# CS301_14.net
KiCad netlist of a schematic drawn in Altium Designer
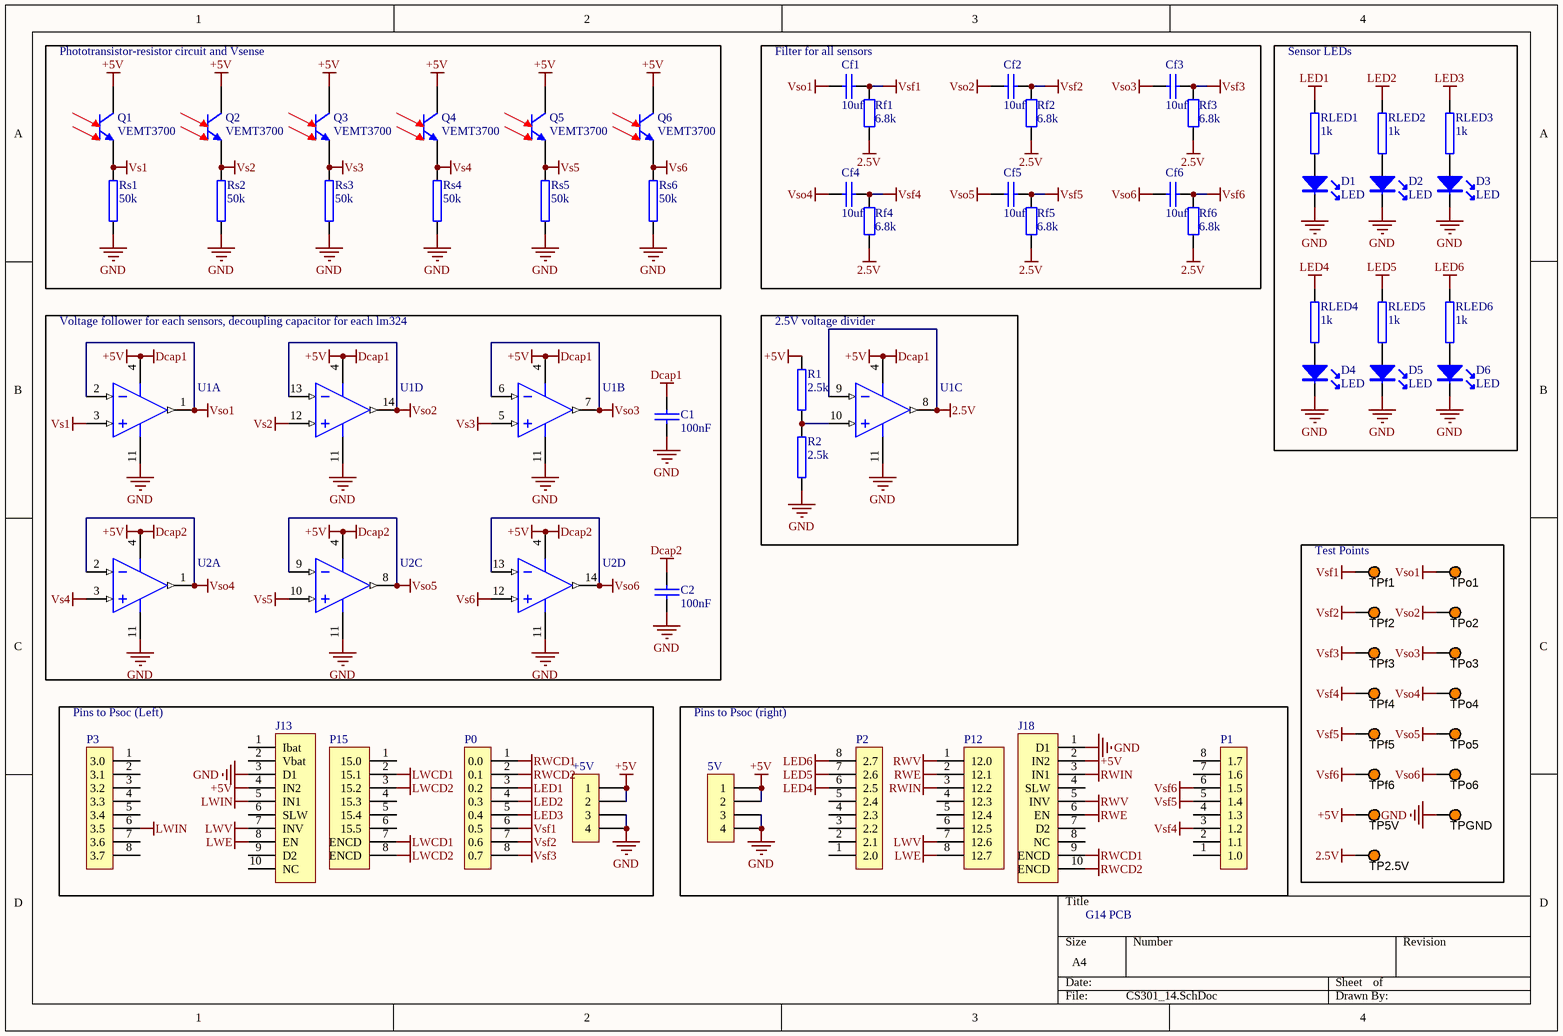
[diagram p0: CS301_14.SchDoc]

(export (version "E")
  (design (tool "Eeschema 10.0.6"))
  (components
    (comp (ref "+5V")
      (value "5V")
      (footprint "IDC4")
      (description "Connector")
      (libsource (lib "Miscellaneous Devices") (part "CON4"))
    )
    (comp (ref "5V")
      (value "5V")
      (footprint "IDC4")
      (description "Connector")
      (libsource (lib "Miscellaneous Devices") (part "CON4"))
    )
    (comp (ref "C1")
      (value "100nF")
      (footprint "CCAP-5P0")
      (description "TH ceramic capacitor with 5mm pitch")
      (libsource (lib "EE209_SchLib") (part "CerCap_TH_5P0"))
    )
    (comp (ref "C2")
      (value "100nF")
      (footprint "CCAP-5P0")
      (description "TH ceramic capacitor with 5mm pitch")
      (libsource (lib "EE209_SchLib") (part "CerCap_TH_5P0"))
    )
    (comp (ref "Cf1")
      (value "10uf")
      (footprint "CCAP-5P0")
      (description "TH ceramic capacitor with 5mm pitch")
      (libsource (lib "EE209_SchLib") (part "CerCap_TH_5P0"))
    )
    (comp (ref "Cf2")
      (value "10uf")
      (footprint "CCAP-5P0")
      (description "TH ceramic capacitor with 5mm pitch")
      (libsource (lib "EE209_SchLib") (part "CerCap_TH_5P0"))
    )
    (comp (ref "Cf3")
      (value "10uf")
      (footprint "CCAP-5P0")
      (description "TH ceramic capacitor with 5mm pitch")
      (libsource (lib "EE209_SchLib") (part "CerCap_TH_5P0"))
    )
    (comp (ref "Cf4")
      (value "10uf")
      (footprint "CCAP-5P0")
      (description "TH ceramic capacitor with 5mm pitch")
      (libsource (lib "EE209_SchLib") (part "CerCap_TH_5P0"))
    )
    (comp (ref "Cf5")
      (value "10uf")
      (footprint "CCAP-5P0")
      (description "TH ceramic capacitor with 5mm pitch")
      (libsource (lib "EE209_SchLib") (part "CerCap_TH_5P0"))
    )
    (comp (ref "Cf6")
      (value "10uf")
      (footprint "CCAP-5P0")
      (description "TH ceramic capacitor with 5mm pitch")
      (libsource (lib "EE209_SchLib") (part "CerCap_TH_5P0"))
    )
    (comp (ref "D1") (value "LED") (footprint "LED0.1/5MM") (libsource (lib "COMSYS301") (part "LED")))
    (comp (ref "D2") (value "LED") (footprint "LED0.1/5MM") (libsource (lib "COMSYS301") (part "LED")))
    (comp (ref "D3") (value "LED") (footprint "LED0.1/5MM") (libsource (lib "COMSYS301") (part "LED")))
    (comp (ref "D4") (value "LED") (footprint "LED0.1/5MM") (libsource (lib "COMSYS301") (part "LED")))
    (comp (ref "D5") (value "LED") (footprint "LED0.1/5MM") (libsource (lib "COMSYS301") (part "LED")))
    (comp (ref "D6") (value "LED") (footprint "LED0.1/5MM") (libsource (lib "COMSYS301") (part "LED")))
    (comp (ref "J13")
      (value "CON10")
      (footprint "idc10")
      (description "Connector")
      (libsource (lib "") (part "CON10_1"))
    )
    (comp (ref "J18")
      (value "CON10")
      (footprint "IDC10")
      (description "Connector")
      (libsource (lib "Miscellaneous Devices") (part "CON10"))
    )
    (comp (ref "P0")
      (value "P0")
      (footprint "idc8")
      (description "Connector")
      (libsource (lib "Miscellaneous Devices") (part "CON8"))
    )
    (comp (ref "P1")
      (value "P1")
      (footprint "idc8")
      (description "Connector")
      (libsource (lib "") (part "CON8_2"))
    )
    (comp (ref "P2")
      (value "P2")
      (footprint "idc8")
      (description "Connector")
      (libsource (lib "") (part "CON8_1"))
    )
    (comp (ref "P3")
      (value "P3")
      (footprint "idc8")
      (description "Connector")
      (libsource (lib "Miscellaneous Devices") (part "CON8"))
    )
    (comp (ref "P12")
      (value "P12")
      (footprint "idc8")
      (description "Connector")
      (libsource (lib "Miscellaneous Devices") (part "CON8_1"))
    )
    (comp (ref "P15")
      (value "P15")
      (footprint "idc8")
      (description "Connector")
      (libsource (lib "") (part "CON8_1_1"))
    )
    (comp (ref "Q1")
      (value "VEMT3700")
      (footprint "VEMT3700")
      (description "Silicon NPN Phototransistor")
      (libsource (lib "COMSYS301") (part "VEMT3700"))
    )
    (comp (ref "Q2")
      (value "VEMT3700")
      (footprint "VEMT3700")
      (description "Silicon NPN Phototransistor")
      (libsource (lib "COMSYS301") (part "VEMT3700"))
    )
    (comp (ref "Q3")
      (value "VEMT3700")
      (footprint "VEMT3700")
      (description "Silicon NPN Phototransistor")
      (libsource (lib "COMSYS301") (part "VEMT3700"))
    )
    (comp (ref "Q4")
      (value "VEMT3700")
      (footprint "VEMT3700")
      (description "Silicon NPN Phototransistor")
      (libsource (lib "COMSYS301") (part "VEMT3700"))
    )
    (comp (ref "Q5")
      (value "VEMT3700")
      (footprint "VEMT3700")
      (description "Silicon NPN Phototransistor")
      (libsource (lib "COMSYS301") (part "VEMT3700"))
    )
    (comp (ref "Q6")
      (value "VEMT3700")
      (footprint "VEMT3700")
      (description "Silicon NPN Phototransistor")
      (libsource (lib "COMSYS301") (part "VEMT3700"))
    )
    (comp (ref "R1") (value "2.5k") (footprint "AXIAL0.4") (libsource (lib "COMSYS301") (part "RES2")))
    (comp (ref "R2") (value "2.5k") (footprint "AXIAL0.4") (libsource (lib "COMSYS301") (part "RES2")))
    (comp (ref "Rf1")
      (value "6.8k")
      (footprint "AXIAL-0.4")
      (description "Through hole resistor")
      (fields (field (name "PUBLISHER") "Altium Limited"))
      (libsource (lib "EE209_SchLib") (part "Res_TH_0AX4"))
    )
    (comp (ref "Rf2")
      (value "6.8k")
      (footprint "AXIAL-0.4")
      (description "Through hole resistor")
      (fields (field (name "PUBLISHER") "Altium Limited"))
      (libsource (lib "EE209_SchLib") (part "Res_TH_0AX4"))
    )
    (comp (ref "Rf3")
      (value "6.8k")
      (footprint "AXIAL-0.4")
      (description "Through hole resistor")
      (fields (field (name "PUBLISHER") "Altium Limited"))
      (libsource (lib "EE209_SchLib") (part "Res_TH_0AX4"))
    )
    (comp (ref "Rf4")
      (value "6.8k")
      (footprint "AXIAL-0.4")
      (description "Through hole resistor")
      (fields (field (name "PUBLISHER") "Altium Limited"))
      (libsource (lib "EE209_SchLib") (part "Res_TH_0AX4"))
    )
    (comp (ref "Rf5")
      (value "6.8k")
      (footprint "AXIAL-0.4")
      (description "Through hole resistor")
      (fields (field (name "PUBLISHER") "Altium Limited"))
      (libsource (lib "EE209_SchLib") (part "Res_TH_0AX4"))
    )
    (comp (ref "Rf6")
      (value "6.8k")
      (footprint "AXIAL-0.4")
      (description "Through hole resistor")
      (fields (field (name "PUBLISHER") "Altium Limited"))
      (libsource (lib "EE209_SchLib") (part "Res_TH_0AX4"))
    )
    (comp (ref "RLED1") (value "1k") (footprint "AXIAL0.4") (libsource (lib "COMSYS301") (part "RES2")))
    (comp (ref "RLED2") (value "1k") (footprint "AXIAL0.4") (libsource (lib "COMSYS301") (part "RES2")))
    (comp (ref "RLED3") (value "1k") (footprint "AXIAL0.4") (libsource (lib "COMSYS301") (part "RES2")))
    (comp (ref "RLED4") (value "1k") (footprint "AXIAL0.4") (libsource (lib "COMSYS301") (part "RES2")))
    (comp (ref "RLED5") (value "1k") (footprint "AXIAL0.4") (libsource (lib "COMSYS301") (part "RES2")))
    (comp (ref "RLED6") (value "1k") (footprint "AXIAL0.4") (libsource (lib "COMSYS301") (part "RES2")))
    (comp (ref "Rs1") (value "50k") (footprint "AXIAL0.4") (libsource (lib "COMSYS301") (part "RES2")))
    (comp (ref "Rs2") (value "50k") (footprint "AXIAL0.4") (libsource (lib "COMSYS301") (part "RES2")))
    (comp (ref "Rs3") (value "50k") (footprint "AXIAL0.4") (libsource (lib "COMSYS301") (part "RES2")))
    (comp (ref "Rs4") (value "50k") (footprint "AXIAL0.4") (libsource (lib "COMSYS301") (part "RES2")))
    (comp (ref "Rs5") (value "50k") (footprint "AXIAL0.4") (libsource (lib "COMSYS301") (part "RES2")))
    (comp (ref "Rs6") (value "50k") (footprint "AXIAL0.4") (libsource (lib "COMSYS301") (part "RES2")))
    (comp (ref "TP2.5V")
      (value "5003")
      (footprint "EE209_PcbLib:TP_TH")
      (description "Test Point, Orange, 1-Pin THD, RoHS")
      (libsource (lib "EE209_SchLib") (part "TestPoint"))
    )
    (comp (ref "TP5V")
      (value "5003")
      (footprint "EE209_PcbLib:TP_TH")
      (description "Test Point, Orange, 1-Pin THD, RoHS")
      (libsource (lib "EE209_SchLib") (part "TestPoint"))
    )
    (comp (ref "TPf1")
      (value "5003")
      (footprint "EE209_PcbLib:TP_TH")
      (description "Test Point, Orange, 1-Pin THD, RoHS")
      (libsource (lib "EE209_SchLib") (part "TestPoint"))
    )
    (comp (ref "TPf2")
      (value "5003")
      (footprint "EE209_PcbLib:TP_TH")
      (description "Test Point, Orange, 1-Pin THD, RoHS")
      (libsource (lib "EE209_SchLib") (part "TestPoint"))
    )
    (comp (ref "TPf3")
      (value "5003")
      (footprint "EE209_PcbLib:TP_TH")
      (description "Test Point, Orange, 1-Pin THD, RoHS")
      (libsource (lib "EE209_SchLib") (part "TestPoint"))
    )
    (comp (ref "TPf4")
      (value "5003")
      (footprint "EE209_PcbLib:TP_TH")
      (description "Test Point, Orange, 1-Pin THD, RoHS")
      (libsource (lib "EE209_SchLib") (part "TestPoint"))
    )
    (comp (ref "TPf5")
      (value "5003")
      (footprint "EE209_PcbLib:TP_TH")
      (description "Test Point, Orange, 1-Pin THD, RoHS")
      (libsource (lib "EE209_SchLib") (part "TestPoint"))
    )
    (comp (ref "TPf6")
      (value "5003")
      (footprint "EE209_PcbLib:TP_TH")
      (description "Test Point, Orange, 1-Pin THD, RoHS")
      (libsource (lib "EE209_SchLib") (part "TestPoint"))
    )
    (comp (ref "TPGND")
      (value "5003")
      (footprint "EE209_PcbLib:TP_TH")
      (description "Test Point, Orange, 1-Pin THD, RoHS")
      (libsource (lib "EE209_SchLib") (part "TestPoint"))
    )
    (comp (ref "TPo1")
      (value "5003")
      (footprint "EE209_PcbLib:TP_TH")
      (description "Test Point, Orange, 1-Pin THD, RoHS")
      (libsource (lib "EE209_SchLib") (part "TestPoint"))
    )
    (comp (ref "TPo2")
      (value "5003")
      (footprint "EE209_PcbLib:TP_TH")
      (description "Test Point, Orange, 1-Pin THD, RoHS")
      (libsource (lib "EE209_SchLib") (part "TestPoint"))
    )
    (comp (ref "TPo3")
      (value "5003")
      (footprint "EE209_PcbLib:TP_TH")
      (description "Test Point, Orange, 1-Pin THD, RoHS")
      (libsource (lib "EE209_SchLib") (part "TestPoint"))
    )
    (comp (ref "TPo4")
      (value "5003")
      (footprint "EE209_PcbLib:TP_TH")
      (description "Test Point, Orange, 1-Pin THD, RoHS")
      (libsource (lib "EE209_SchLib") (part "TestPoint"))
    )
    (comp (ref "TPo5")
      (value "5003")
      (footprint "EE209_PcbLib:TP_TH")
      (description "Test Point, Orange, 1-Pin THD, RoHS")
      (libsource (lib "EE209_SchLib") (part "TestPoint"))
    )
    (comp (ref "TPo6")
      (value "5003")
      (footprint "EE209_PcbLib:TP_TH")
      (description "Test Point, Orange, 1-Pin THD, RoHS")
      (libsource (lib "EE209_SchLib") (part "TestPoint"))
    )
    (comp (ref "U1")
      (value "LM324")
      (footprint "DIP-14")
      (description "IC OPAMP GP 14DIP")
      (fields
        (field (name "MANUFACTURER") "ON Semiconductor")
        (field (name "MANUFACTURER PART NUMBER") "LM324N")
      )
      (libsource (lib "EE209_SchLib") (part "LM324N_TH_DIP16"))
    )
    (comp (ref "U2")
      (value "LM324")
      (footprint "DIP-14")
      (description "IC OPAMP GP 14DIP")
      (fields
        (field (name "MANUFACTURER") "ON Semiconductor")
        (field (name "MANUFACTURER PART NUMBER") "LM324N")
      )
      (libsource (lib "EE209_SchLib") (part "LM324N_TH_DIP16"))
    )
  )
  (nets
    (net (code "1") (name "+5V") (class "Default")
      (node (ref "+5V") (pin "1") (pinfunction "1_1") (pintype "passive"))
      (node (ref "+5V") (pin "2") (pinfunction "2_2") (pintype "passive"))
      (node (ref "5V") (pin "1") (pinfunction "1_1") (pintype "passive"))
      (node (ref "5V") (pin "2") (pinfunction "2_2") (pintype "passive"))
      (node (ref "C1") (pin "1") (pinfunction "1_1") (pintype "passive"))
      (node (ref "C2") (pin "1") (pinfunction "1_1") (pintype "passive"))
      (node (ref "J13") (pin "4") (pinfunction "IN2_4") (pintype "passive"))
      (node (ref "J18") (pin "2") (pinfunction "IN2_2") (pintype "passive"))
      (node (ref "Q1") (pin "1") (pinfunction "C_1") (pintype "passive"))
      (node (ref "Q2") (pin "1") (pinfunction "C_1") (pintype "passive"))
      (node (ref "Q3") (pin "1") (pinfunction "C_1") (pintype "passive"))
      (node (ref "Q4") (pin "1") (pinfunction "C_1") (pintype "passive"))
      (node (ref "Q5") (pin "1") (pinfunction "C_1") (pintype "passive"))
      (node (ref "Q6") (pin "1") (pinfunction "C_1") (pintype "passive"))
      (node (ref "R1") (pin "1") (pinfunction "1_1") (pintype "passive"))
      (node (ref "TP5V") (pin "1") (pinfunction "1_1") (pintype "passive"))
      (node (ref "U1") (pin "4") (pinfunction "VDD_4") (pintype "power_in"))
      (node (ref "U2") (pin "4") (pinfunction "VDD_4") (pintype "power_in"))
    )
    (net (code "2") (name "2.5V") (class "Default")
      (node (ref "Rf1") (pin "1") (pinfunction "1_1") (pintype "passive"))
      (node (ref "Rf2") (pin "1") (pinfunction "1_1") (pintype "passive"))
      (node (ref "Rf3") (pin "1") (pinfunction "1_1") (pintype "passive"))
      (node (ref "Rf4") (pin "1") (pinfunction "1_1") (pintype "passive"))
      (node (ref "Rf5") (pin "1") (pinfunction "1_1") (pintype "passive"))
      (node (ref "Rf6") (pin "1") (pinfunction "1_1") (pintype "passive"))
      (node (ref "TP2.5V") (pin "1") (pinfunction "1_1") (pintype "passive"))
      (node (ref "U1") (pin "8") (pinfunction "VOUTC_8") (pintype "output"))
      (node (ref "U1") (pin "9") (pinfunction "VINC-_9") (pintype "input"))
    )
    (net (code "3") (name "GND") (class "Default")
      (node (ref "+5V") (pin "3") (pinfunction "3_3") (pintype "passive"))
      (node (ref "+5V") (pin "4") (pinfunction "4_4") (pintype "passive"))
      (node (ref "5V") (pin "3") (pinfunction "3_3") (pintype "passive"))
      (node (ref "5V") (pin "4") (pinfunction "4_4") (pintype "passive"))
      (node (ref "C1") (pin "2") (pinfunction "2_2") (pintype "passive"))
      (node (ref "C2") (pin "2") (pinfunction "2_2") (pintype "passive"))
      (node (ref "D1") (pin "K") (pinfunction "2_K") (pintype "passive"))
      (node (ref "D2") (pin "K") (pinfunction "2_K") (pintype "passive"))
      (node (ref "D3") (pin "K") (pinfunction "2_K") (pintype "passive"))
      (node (ref "D4") (pin "K") (pinfunction "2_K") (pintype "passive"))
      (node (ref "D5") (pin "K") (pinfunction "2_K") (pintype "passive"))
      (node (ref "D6") (pin "K") (pinfunction "2_K") (pintype "passive"))
      (node (ref "J13") (pin "3") (pinfunction "D1_3") (pintype "passive"))
      (node (ref "J18") (pin "1") (pinfunction "D1_1") (pintype "passive"))
      (node (ref "R2") (pin "2") (pinfunction "2_2") (pintype "passive"))
      (node (ref "Rs1") (pin "2") (pinfunction "2_2") (pintype "passive"))
      (node (ref "Rs2") (pin "2") (pinfunction "2_2") (pintype "passive"))
      (node (ref "Rs3") (pin "2") (pinfunction "2_2") (pintype "passive"))
      (node (ref "Rs4") (pin "2") (pinfunction "2_2") (pintype "passive"))
      (node (ref "Rs5") (pin "2") (pinfunction "2_2") (pintype "passive"))
      (node (ref "Rs6") (pin "2") (pinfunction "2_2") (pintype "passive"))
      (node (ref "TPGND") (pin "1") (pinfunction "1_1") (pintype "passive"))
      (node (ref "U1") (pin "11") (pinfunction "VSS_11") (pintype "power_in"))
      (node (ref "U2") (pin "11") (pinfunction "VSS_11") (pintype "power_in"))
    )
    (net (code "4") (name "LED1") (class "Default")
      (node (ref "P0") (pin "3") (pinfunction "3.2_3") (pintype "passive"))
      (node (ref "RLED1") (pin "1") (pinfunction "1_1") (pintype "passive"))
    )
    (net (code "5") (name "LED2") (class "Default")
      (node (ref "P0") (pin "4") (pinfunction "3.3_4") (pintype "passive"))
      (node (ref "RLED2") (pin "1") (pinfunction "1_1") (pintype "passive"))
    )
    (net (code "6") (name "LED3") (class "Default")
      (node (ref "P0") (pin "5") (pinfunction "3.4_5") (pintype "passive"))
      (node (ref "RLED3") (pin "1") (pinfunction "1_1") (pintype "passive"))
    )
    (net (code "7") (name "LED4") (class "Default")
      (node (ref "P2") (pin "6") (pinfunction "2.5_6") (pintype "passive"))
      (node (ref "RLED4") (pin "1") (pinfunction "1_1") (pintype "passive"))
    )
    (net (code "8") (name "LED5") (class "Default")
      (node (ref "P2") (pin "7") (pinfunction "2.6_7") (pintype "passive"))
      (node (ref "RLED5") (pin "1") (pinfunction "1_1") (pintype "passive"))
    )
    (net (code "9") (name "LED6") (class "Default")
      (node (ref "P2") (pin "8") (pinfunction "2.7_8") (pintype "passive"))
      (node (ref "RLED6") (pin "1") (pinfunction "1_1") (pintype "passive"))
    )
    (net (code "10") (name "LWCD1") (class "Default")
      (node (ref "P15") (pin "2") (pinfunction "15.1_2") (pintype "passive"))
      (node (ref "P15") (pin "7") (pinfunction "ENCD_7") (pintype "passive"))
    )
    (net (code "11") (name "LWCD2") (class "Default")
      (node (ref "P15") (pin "3") (pinfunction "15.2_3") (pintype "passive"))
      (node (ref "P15") (pin "8") (pinfunction "ENCD_8") (pintype "passive"))
    )
    (net (code "12") (name "LWE") (class "Default")
      (node (ref "J13") (pin "8") (pinfunction "EN_8") (pintype "passive"))
      (node (ref "P12") (pin "8") (pinfunction "12.7_8") (pintype "passive"))
    )
    (net (code "13") (name "LWIN") (class "Default")
      (node (ref "J13") (pin "5") (pinfunction "IN1_5") (pintype "passive"))
      (node (ref "P3") (pin "6") (pinfunction "3.5_6") (pintype "passive"))
    )
    (net (code "14") (name "LWV") (class "Default")
      (node (ref "J13") (pin "7") (pinfunction "INV_7") (pintype "passive"))
      (node (ref "P12") (pin "7") (pinfunction "12.6_7") (pintype "passive"))
    )
    (net (code "15") (name "Net-(D1-1)") (class "Default")
      (node (ref "D1") (pin "A") (pinfunction "1_A") (pintype "passive"))
      (node (ref "RLED1") (pin "2") (pinfunction "2_2") (pintype "passive"))
    )
    (net (code "16") (name "Net-(D2-1)") (class "Default")
      (node (ref "D2") (pin "A") (pinfunction "1_A") (pintype "passive"))
      (node (ref "RLED2") (pin "2") (pinfunction "2_2") (pintype "passive"))
    )
    (net (code "17") (name "Net-(D3-1)") (class "Default")
      (node (ref "D3") (pin "A") (pinfunction "1_A") (pintype "passive"))
      (node (ref "RLED3") (pin "2") (pinfunction "2_2") (pintype "passive"))
    )
    (net (code "18") (name "Net-(D4-1)") (class "Default")
      (node (ref "D4") (pin "A") (pinfunction "1_A") (pintype "passive"))
      (node (ref "RLED4") (pin "2") (pinfunction "2_2") (pintype "passive"))
    )
    (net (code "19") (name "Net-(D5-1)") (class "Default")
      (node (ref "D5") (pin "A") (pinfunction "1_A") (pintype "passive"))
      (node (ref "RLED5") (pin "2") (pinfunction "2_2") (pintype "passive"))
    )
    (net (code "20") (name "Net-(D6-1)") (class "Default")
      (node (ref "D6") (pin "A") (pinfunction "1_A") (pintype "passive"))
      (node (ref "RLED6") (pin "2") (pinfunction "2_2") (pintype "passive"))
    )
    (net (code "21") (name "Net-(U1C-VINC+)") (class "Default")
      (node (ref "R1") (pin "2") (pinfunction "2_2") (pintype "passive"))
      (node (ref "R2") (pin "1") (pinfunction "1_1") (pintype "passive"))
      (node (ref "U1") (pin "10") (pinfunction "VINC+_10") (pintype "input"))
    )
    (net (code "22") (name "RWCD1") (class "Default")
      (node (ref "J18") (pin "9") (pinfunction "ENCD_9") (pintype "passive"))
      (node (ref "P0") (pin "1") (pinfunction "3.0_1") (pintype "passive"))
    )
    (net (code "23") (name "RWCD2") (class "Default")
      (node (ref "J18") (pin "10") (pinfunction "ENCD_10") (pintype "passive"))
      (node (ref "P0") (pin "2") (pinfunction "3.1_2") (pintype "passive"))
    )
    (net (code "24") (name "RWE") (class "Default")
      (node (ref "J18") (pin "6") (pinfunction "EN_6") (pintype "passive"))
      (node (ref "P12") (pin "2") (pinfunction "12.1_2") (pintype "passive"))
    )
    (net (code "25") (name "RWIN") (class "Default")
      (node (ref "J18") (pin "3") (pinfunction "IN1_3") (pintype "passive"))
      (node (ref "P12") (pin "3") (pinfunction "12.2_3") (pintype "passive"))
    )
    (net (code "26") (name "RWV") (class "Default")
      (node (ref "J18") (pin "5") (pinfunction "INV_5") (pintype "passive"))
      (node (ref "P12") (pin "1") (pinfunction "12.0_1") (pintype "passive"))
    )
    (net (code "27") (name "Vs1") (class "Default")
      (node (ref "Q1") (pin "2") (pinfunction "E_2") (pintype "passive"))
      (node (ref "Rs1") (pin "1") (pinfunction "1_1") (pintype "passive"))
      (node (ref "U1") (pin "3") (pinfunction "VINA+_3") (pintype "input"))
    )
    (net (code "28") (name "Vs2") (class "Default")
      (node (ref "Q2") (pin "2") (pinfunction "E_2") (pintype "passive"))
      (node (ref "Rs2") (pin "1") (pinfunction "1_1") (pintype "passive"))
      (node (ref "U1") (pin "12") (pinfunction "VIND+_12") (pintype "input"))
    )
    (net (code "29") (name "Vs3") (class "Default")
      (node (ref "Q3") (pin "2") (pinfunction "E_2") (pintype "passive"))
      (node (ref "Rs3") (pin "1") (pinfunction "1_1") (pintype "passive"))
      (node (ref "U1") (pin "5") (pinfunction "VINB+_5") (pintype "input"))
    )
    (net (code "30") (name "Vs4") (class "Default")
      (node (ref "Q4") (pin "2") (pinfunction "E_2") (pintype "passive"))
      (node (ref "Rs4") (pin "1") (pinfunction "1_1") (pintype "passive"))
      (node (ref "U2") (pin "3") (pinfunction "VINA+_3") (pintype "input"))
    )
    (net (code "31") (name "Vs5") (class "Default")
      (node (ref "Q5") (pin "2") (pinfunction "E_2") (pintype "passive"))
      (node (ref "Rs5") (pin "1") (pinfunction "1_1") (pintype "passive"))
      (node (ref "U2") (pin "10") (pinfunction "VINC+_10") (pintype "input"))
    )
    (net (code "32") (name "Vs6") (class "Default")
      (node (ref "Q6") (pin "2") (pinfunction "E_2") (pintype "passive"))
      (node (ref "Rs6") (pin "1") (pinfunction "1_1") (pintype "passive"))
      (node (ref "U2") (pin "12") (pinfunction "VIND+_12") (pintype "input"))
    )
    (net (code "33") (name "Vsf1") (class "Default")
      (node (ref "Cf1") (pin "2") (pinfunction "2_2") (pintype "passive"))
      (node (ref "P0") (pin "6") (pinfunction "3.5_6") (pintype "passive"))
      (node (ref "Rf1") (pin "2") (pinfunction "2_2") (pintype "passive"))
      (node (ref "TPf1") (pin "1") (pinfunction "1_1") (pintype "passive"))
    )
    (net (code "34") (name "Vsf2") (class "Default")
      (node (ref "Cf2") (pin "2") (pinfunction "2_2") (pintype "passive"))
      (node (ref "P0") (pin "7") (pinfunction "3.6_7") (pintype "passive"))
      (node (ref "Rf2") (pin "2") (pinfunction "2_2") (pintype "passive"))
      (node (ref "TPf2") (pin "1") (pinfunction "1_1") (pintype "passive"))
    )
    (net (code "35") (name "Vsf3") (class "Default")
      (node (ref "Cf3") (pin "2") (pinfunction "2_2") (pintype "passive"))
      (node (ref "P0") (pin "8") (pinfunction "3.7_8") (pintype "passive"))
      (node (ref "Rf3") (pin "2") (pinfunction "2_2") (pintype "passive"))
      (node (ref "TPf3") (pin "1") (pinfunction "1_1") (pintype "passive"))
    )
    (net (code "36") (name "Vsf4") (class "Default")
      (node (ref "Cf4") (pin "2") (pinfunction "2_2") (pintype "passive"))
      (node (ref "P1") (pin "3") (pinfunction "1.2_3") (pintype "passive"))
      (node (ref "Rf4") (pin "2") (pinfunction "2_2") (pintype "passive"))
      (node (ref "TPf4") (pin "1") (pinfunction "1_1") (pintype "passive"))
    )
    (net (code "37") (name "Vsf5") (class "Default")
      (node (ref "Cf5") (pin "2") (pinfunction "2_2") (pintype "passive"))
      (node (ref "P1") (pin "5") (pinfunction "1.4_5") (pintype "passive"))
      (node (ref "Rf5") (pin "2") (pinfunction "2_2") (pintype "passive"))
      (node (ref "TPf5") (pin "1") (pinfunction "1_1") (pintype "passive"))
    )
    (net (code "38") (name "Vsf6") (class "Default")
      (node (ref "Cf6") (pin "2") (pinfunction "2_2") (pintype "passive"))
      (node (ref "P1") (pin "6") (pinfunction "1.5_6") (pintype "passive"))
      (node (ref "Rf6") (pin "2") (pinfunction "2_2") (pintype "passive"))
      (node (ref "TPf6") (pin "1") (pinfunction "1_1") (pintype "passive"))
    )
    (net (code "39") (name "Vso1") (class "Default")
      (node (ref "Cf1") (pin "1") (pinfunction "1_1") (pintype "passive"))
      (node (ref "TPo1") (pin "1") (pinfunction "1_1") (pintype "passive"))
      (node (ref "U1") (pin "1") (pinfunction "VOUTA_1") (pintype "output"))
      (node (ref "U1") (pin "2") (pinfunction "VINA-_2") (pintype "input"))
    )
    (net (code "40") (name "Vso2") (class "Default")
      (node (ref "Cf2") (pin "1") (pinfunction "1_1") (pintype "passive"))
      (node (ref "TPo2") (pin "1") (pinfunction "1_1") (pintype "passive"))
      (node (ref "U1") (pin "13") (pinfunction "VIND-_13") (pintype "input"))
      (node (ref "U1") (pin "14") (pinfunction "VOUTD_14") (pintype "output"))
    )
    (net (code "41") (name "Vso3") (class "Default")
      (node (ref "Cf3") (pin "1") (pinfunction "1_1") (pintype "passive"))
      (node (ref "TPo3") (pin "1") (pinfunction "1_1") (pintype "passive"))
      (node (ref "U1") (pin "6") (pinfunction "VINB-_6") (pintype "input"))
      (node (ref "U1") (pin "7") (pinfunction "VOUTB_7") (pintype "output"))
    )
    (net (code "42") (name "Vso4") (class "Default")
      (node (ref "Cf4") (pin "1") (pinfunction "1_1") (pintype "passive"))
      (node (ref "TPo4") (pin "1") (pinfunction "1_1") (pintype "passive"))
      (node (ref "U2") (pin "1") (pinfunction "VOUTA_1") (pintype "output"))
      (node (ref "U2") (pin "2") (pinfunction "VINA-_2") (pintype "input"))
    )
    (net (code "43") (name "Vso5") (class "Default")
      (node (ref "Cf5") (pin "1") (pinfunction "1_1") (pintype "passive"))
      (node (ref "TPo5") (pin "1") (pinfunction "1_1") (pintype "passive"))
      (node (ref "U2") (pin "8") (pinfunction "VOUTC_8") (pintype "output"))
      (node (ref "U2") (pin "9") (pinfunction "VINC-_9") (pintype "input"))
    )
    (net (code "44") (name "Vso6") (class "Default")
      (node (ref "Cf6") (pin "1") (pinfunction "1_1") (pintype "passive"))
      (node (ref "TPo6") (pin "1") (pinfunction "1_1") (pintype "passive"))
      (node (ref "U2") (pin "13") (pinfunction "VIND-_13") (pintype "input"))
      (node (ref "U2") (pin "14") (pinfunction "VOUTD_14") (pintype "output"))
    )
    (net (code "45") (name "unconnected-(J13-D2-Pad9)") (class "Default")
      (node (ref "J13") (pin "9") (pinfunction "D2_9") (pintype "passive"))
    )
    (net (code "46") (name "unconnected-(J13-Ibat-Pad1)") (class "Default")
      (node (ref "J13") (pin "1") (pinfunction "Ibat_1") (pintype "passive"))
    )
    (net (code "47") (name "unconnected-(J13-NC-Pad10)") (class "Default")
      (node (ref "J13") (pin "10") (pinfunction "NC_10") (pintype "passive"))
    )
    (net (code "48") (name "unconnected-(J13-SLW-Pad6)") (class "Default")
      (node (ref "J13") (pin "6") (pinfunction "SLW_6") (pintype "passive"))
    )
    (net (code "49") (name "unconnected-(J13-Vbat-Pad2)") (class "Default")
      (node (ref "J13") (pin "2") (pinfunction "Vbat_2") (pintype "passive"))
    )
    (net (code "50") (name "unconnected-(J18-D2-Pad7)") (class "Default")
      (node (ref "J18") (pin "7") (pinfunction "D2_7") (pintype "passive"))
    )
    (net (code "51") (name "unconnected-(J18-NC-Pad8)") (class "Default")
      (node (ref "J18") (pin "8") (pinfunction "NC_8") (pintype "passive"))
    )
    (net (code "52") (name "unconnected-(J18-SLW-Pad4)") (class "Default")
      (node (ref "J18") (pin "4") (pinfunction "SLW_4") (pintype "passive"))
    )
    (net (code "53") (name "unconnected-(P1-1.0-Pad1)") (class "Default")
      (node (ref "P1") (pin "1") (pinfunction "1.0_1") (pintype "passive"))
    )
    (net (code "54") (name "unconnected-(P1-1.1-Pad2)") (class "Default")
      (node (ref "P1") (pin "2") (pinfunction "1.1_2") (pintype "passive"))
    )
    (net (code "55") (name "unconnected-(P1-1.3-Pad4)") (class "Default")
      (node (ref "P1") (pin "4") (pinfunction "1.3_4") (pintype "passive"))
    )
    (net (code "56") (name "unconnected-(P1-1.6-Pad7)") (class "Default")
      (node (ref "P1") (pin "7") (pinfunction "1.6_7") (pintype "passive"))
    )
    (net (code "57") (name "unconnected-(P1-1.7-Pad8)") (class "Default")
      (node (ref "P1") (pin "8") (pinfunction "1.7_8") (pintype "passive"))
    )
    (net (code "58") (name "unconnected-(P2-2.0-Pad1)") (class "Default")
      (node (ref "P2") (pin "1") (pinfunction "2.0_1") (pintype "passive"))
    )
    (net (code "59") (name "unconnected-(P2-2.1-Pad2)") (class "Default")
      (node (ref "P2") (pin "2") (pinfunction "2.1_2") (pintype "passive"))
    )
    (net (code "60") (name "unconnected-(P2-2.2-Pad3)") (class "Default")
      (node (ref "P2") (pin "3") (pinfunction "2.2_3") (pintype "passive"))
    )
    (net (code "61") (name "unconnected-(P2-2.3-Pad4)") (class "Default")
      (node (ref "P2") (pin "4") (pinfunction "2.3_4") (pintype "passive"))
    )
    (net (code "62") (name "unconnected-(P2-2.4-Pad5)") (class "Default")
      (node (ref "P2") (pin "5") (pinfunction "2.4_5") (pintype "passive"))
    )
    (net (code "63") (name "unconnected-(P3-3.0-Pad1)") (class "Default")
      (node (ref "P3") (pin "1") (pinfunction "3.0_1") (pintype "passive"))
    )
    (net (code "64") (name "unconnected-(P3-3.1-Pad2)") (class "Default")
      (node (ref "P3") (pin "2") (pinfunction "3.1_2") (pintype "passive"))
    )
    (net (code "65") (name "unconnected-(P3-3.2-Pad3)") (class "Default")
      (node (ref "P3") (pin "3") (pinfunction "3.2_3") (pintype "passive"))
    )
    (net (code "66") (name "unconnected-(P3-3.3-Pad4)") (class "Default")
      (node (ref "P3") (pin "4") (pinfunction "3.3_4") (pintype "passive"))
    )
    (net (code "67") (name "unconnected-(P3-3.4-Pad5)") (class "Default")
      (node (ref "P3") (pin "5") (pinfunction "3.4_5") (pintype "passive"))
    )
    (net (code "68") (name "unconnected-(P3-3.6-Pad7)") (class "Default")
      (node (ref "P3") (pin "7") (pinfunction "3.6_7") (pintype "passive"))
    )
    (net (code "69") (name "unconnected-(P3-3.7-Pad8)") (class "Default")
      (node (ref "P3") (pin "8") (pinfunction "3.7_8") (pintype "passive"))
    )
    (net (code "70") (name "unconnected-(P12-12.3-Pad4)") (class "Default")
      (node (ref "P12") (pin "4") (pinfunction "12.3_4") (pintype "passive"))
    )
    (net (code "71") (name "unconnected-(P12-12.4-Pad5)") (class "Default")
      (node (ref "P12") (pin "5") (pinfunction "12.4_5") (pintype "passive"))
    )
    (net (code "72") (name "unconnected-(P12-12.5-Pad6)") (class "Default")
      (node (ref "P12") (pin "6") (pinfunction "12.5_6") (pintype "passive"))
    )
    (net (code "73") (name "unconnected-(P15-15.0-Pad1)") (class "Default")
      (node (ref "P15") (pin "1") (pinfunction "15.0_1") (pintype "passive"))
    )
    (net (code "74") (name "unconnected-(P15-15.3-Pad4)") (class "Default")
      (node (ref "P15") (pin "4") (pinfunction "15.3_4") (pintype "passive"))
    )
    (net (code "75") (name "unconnected-(P15-15.4-Pad5)") (class "Default")
      (node (ref "P15") (pin "5") (pinfunction "15.4_5") (pintype "passive"))
    )
    (net (code "76") (name "unconnected-(P15-15.5-Pad6)") (class "Default")
      (node (ref "P15") (pin "6") (pinfunction "15.5_6") (pintype "passive"))
    )
  )
)
